# rev_beta_03_1H_smd_ab4.net
KiCad netlist of a schematic drawn in EAGLE
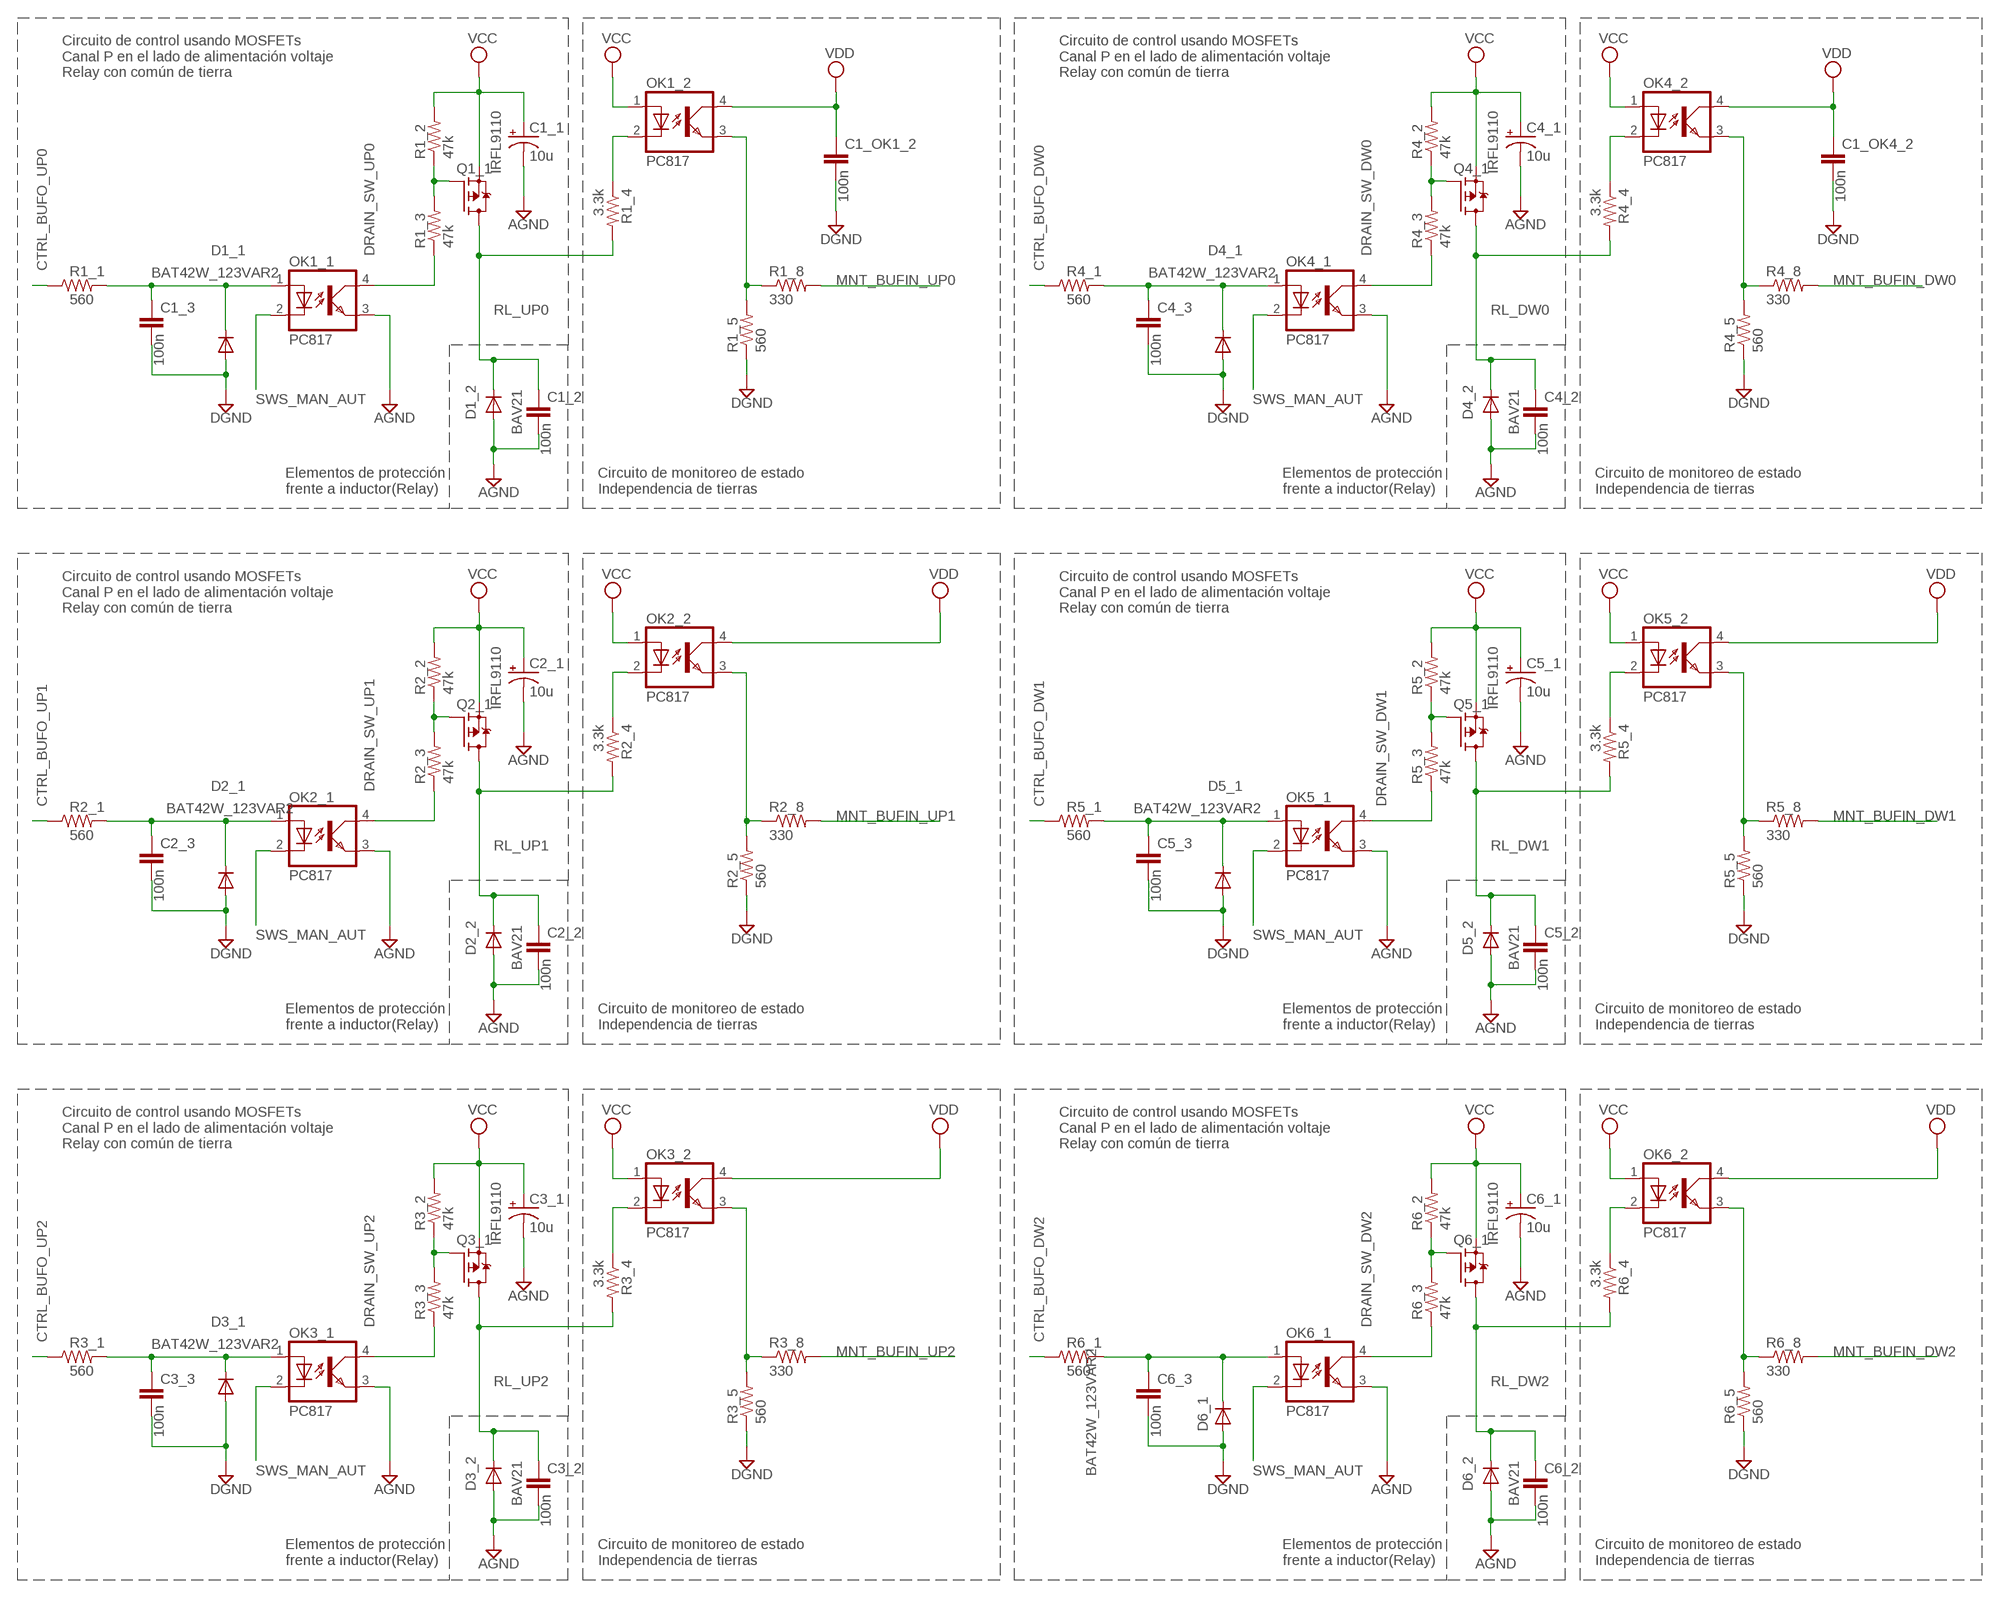
[diagram p0: schematic, sheet 1]
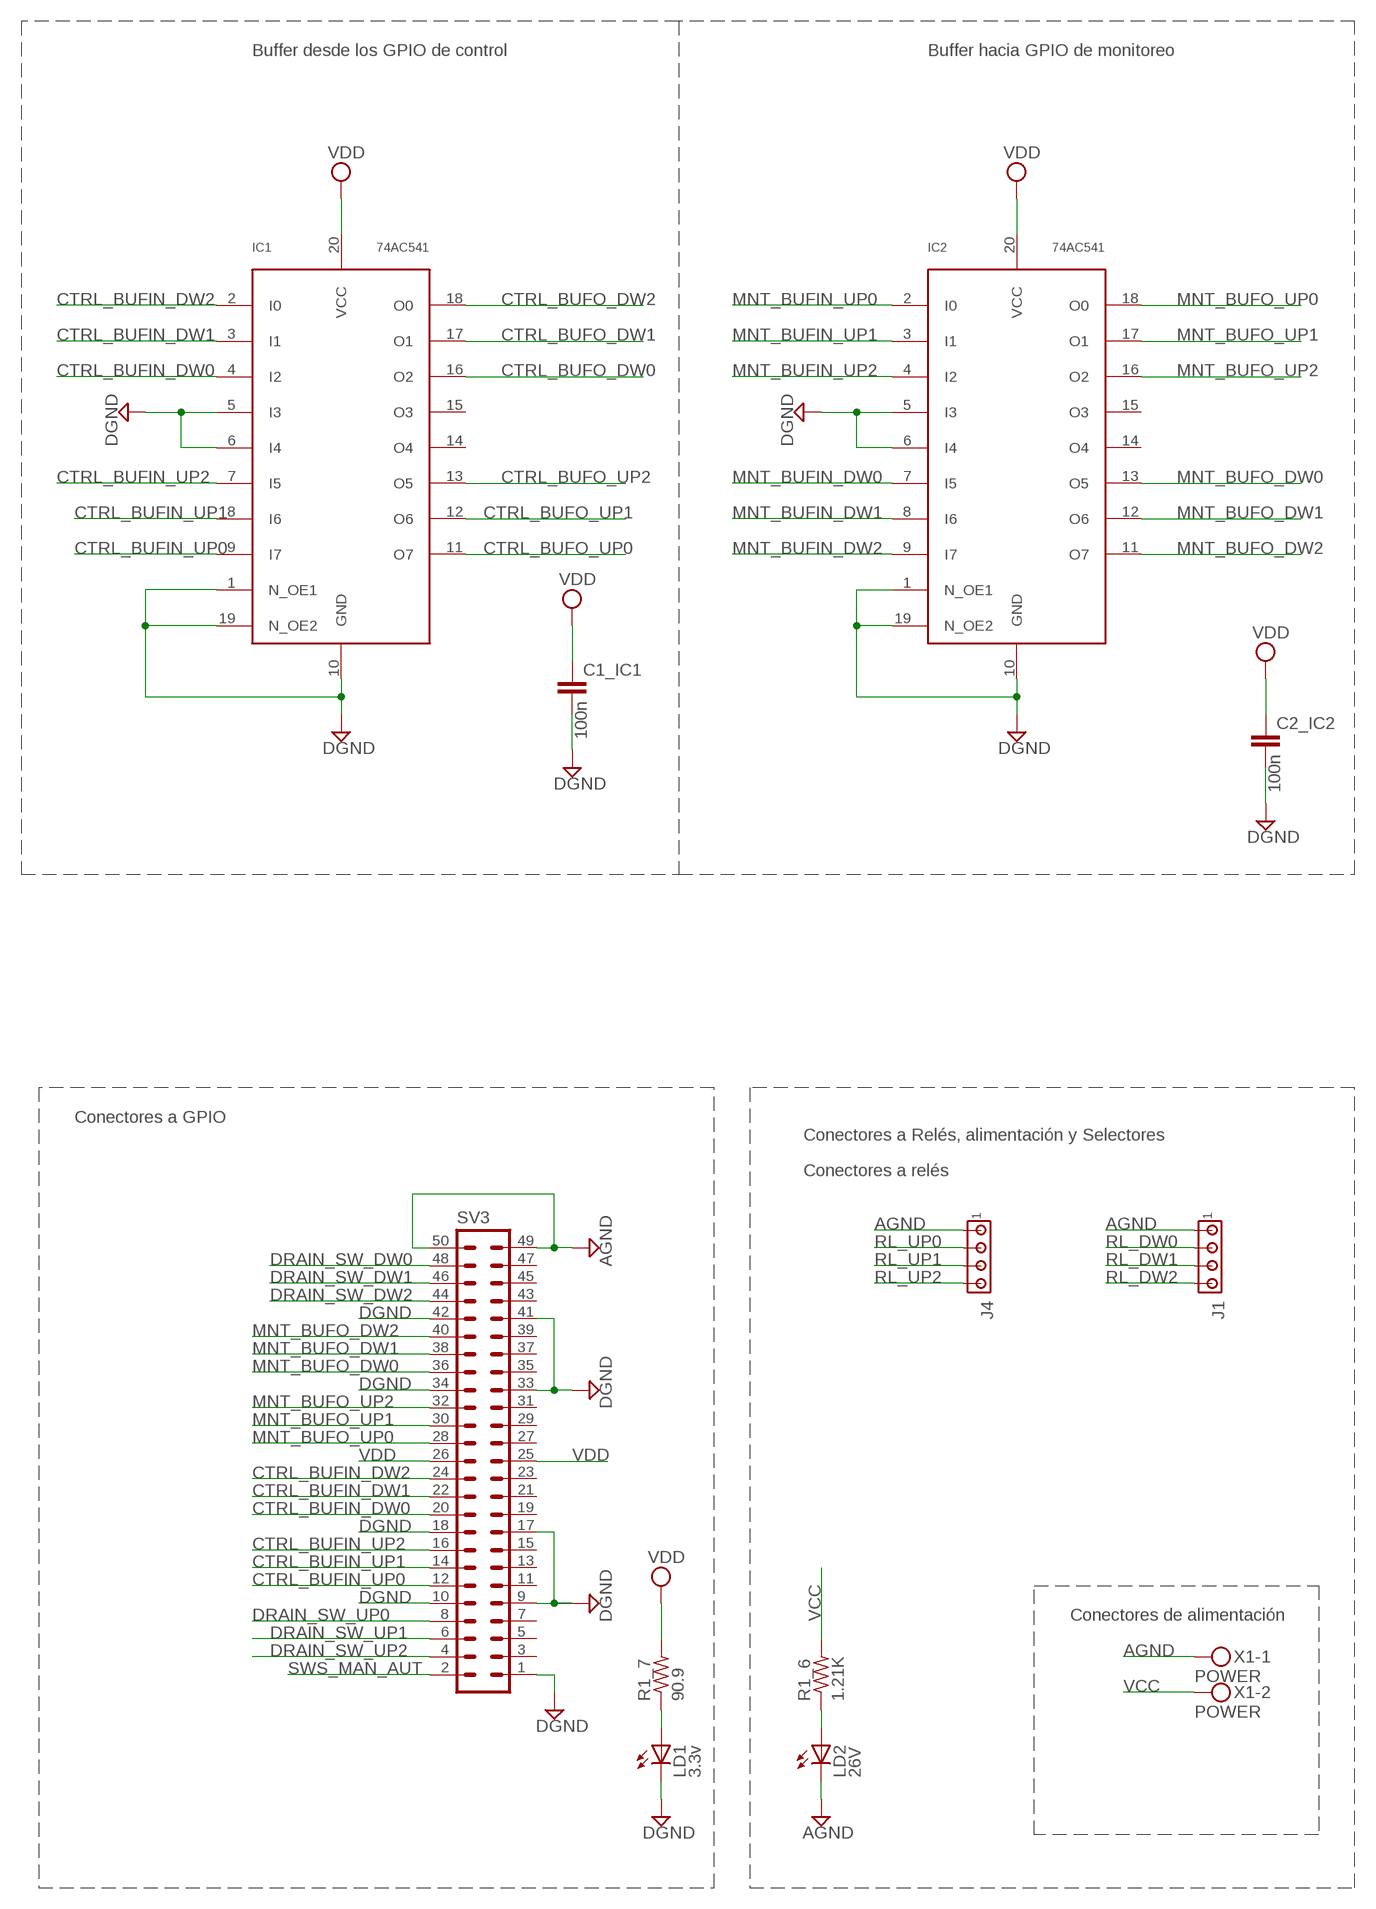
[diagram p1: schematic, sheet 2]

(export (version "E")
  (design (tool "Eeschema 10.0.6"))
  (components
    (comp (ref "C1_IC1")
      (value "100n")
      (footprint "eagle-import:C1206")
      (libsource (lib "eagle-import") (part "C-EUC1206"))
    )
    (comp (ref "C2_IC2")
      (value "100n")
      (footprint "eagle-import:C1206")
      (libsource (lib "eagle-import") (part "C-EUC1206"))
    )
    (comp (ref "IC1")
      (value "74AC541")
      (footprint "eagle-import:SOIC-20DW")
      (fields (field (name "MPN") "74AC541SC"))
      (libsource (lib "eagle-import") (part "74AC541"))
    )
    (comp (ref "IC2")
      (value "74AC541")
      (footprint "eagle-import:SOIC-20DW")
      (fields (field (name "MPN") "74AC541SC"))
      (libsource (lib "eagle-import") (part "74AC541"))
    )
    (comp (ref "J1")
      (value "MTA04-156")
      (footprint "eagle-import:1X4MTA")
      (libsource (lib "eagle-import") (part "MTA04-156"))
    )
    (comp (ref "J4")
      (value "MTA04-156")
      (footprint "eagle-import:1X4MTA")
      (libsource (lib "eagle-import") (part "MTA04-156"))
    )
    (comp (ref "LD1")
      (value "3.3v")
      (footprint "eagle-import:CHIPLED_0603")
      (libsource (lib "eagle-import") (part "LEDCHIPLED_0603"))
    )
    (comp (ref "LD2")
      (value "26V")
      (footprint "eagle-import:CHIPLED_0603")
      (libsource (lib "eagle-import") (part "LEDCHIPLED_0603"))
    )
    (comp (ref "R1_6")
      (value "1.21K")
      (footprint "eagle-import:R1206")
      (libsource (lib "eagle-import") (part "R-US_R1206"))
    )
    (comp (ref "R1_7")
      (value "90.9")
      (footprint "eagle-import:R1206")
      (libsource (lib "eagle-import") (part "R-US_R1206"))
    )
    (comp (ref "SV3")
      (value "ML50\"")
      (footprint "eagle-import:ML50")
      (libsource (lib "eagle-import") (part "ML50{dblquote}"))
    )
    (comp (ref "X1")
      (value "POWER")
      (footprint "eagle-import:MKDSN1,5_2-5,08")
      (libsource (lib "eagle-import") (part "MKDSN1,5/2-5,08"))
    )
    (comp (ref "C1_1")
      (value "10u")
      (footprint "eagle-import:153CLV-0605")
      (libsource (lib "eagle-import") (part "CPOL-US153CLV-0605"))
    )
    (comp (ref "C1_2")
      (value "100n")
      (footprint "eagle-import:C1206")
      (libsource (lib "eagle-import") (part "C-EUC1206"))
    )
    (comp (ref "C1_3")
      (value "100n")
      (footprint "eagle-import:C1206")
      (libsource (lib "eagle-import") (part "C-EUC1206"))
    )
    (comp (ref "C1_OK1_2")
      (value "100n")
      (footprint "eagle-import:C1206")
      (libsource (lib "eagle-import") (part "C-EUC1206"))
    )
    (comp (ref "C1_OK4_2")
      (value "100n")
      (footprint "eagle-import:C1206")
      (libsource (lib "eagle-import") (part "C-EUC1206"))
    )
    (comp (ref "C2_1")
      (value "10u")
      (footprint "eagle-import:153CLV-0605")
      (libsource (lib "eagle-import") (part "CPOL-US153CLV-0605"))
    )
    (comp (ref "C2_2")
      (value "100n")
      (footprint "eagle-import:C1206")
      (libsource (lib "eagle-import") (part "C-EUC1206"))
    )
    (comp (ref "C2_3")
      (value "100n")
      (footprint "eagle-import:C1206")
      (libsource (lib "eagle-import") (part "C-EUC1206"))
    )
    (comp (ref "C3_1")
      (value "10u")
      (footprint "eagle-import:153CLV-0605")
      (libsource (lib "eagle-import") (part "CPOL-US153CLV-0605"))
    )
    (comp (ref "C3_2")
      (value "100n")
      (footprint "eagle-import:C1206")
      (libsource (lib "eagle-import") (part "C-EUC1206"))
    )
    (comp (ref "C3_3")
      (value "100n")
      (footprint "eagle-import:C1206")
      (libsource (lib "eagle-import") (part "C-EUC1206"))
    )
    (comp (ref "C4_1")
      (value "10u")
      (footprint "eagle-import:153CLV-0605")
      (libsource (lib "eagle-import") (part "CPOL-US153CLV-0605"))
    )
    (comp (ref "C4_2")
      (value "100n")
      (footprint "eagle-import:C1206")
      (libsource (lib "eagle-import") (part "C-EUC1206"))
    )
    (comp (ref "C4_3")
      (value "100n")
      (footprint "eagle-import:C1206")
      (libsource (lib "eagle-import") (part "C-EUC1206"))
    )
    (comp (ref "C5_1")
      (value "10u")
      (footprint "eagle-import:153CLV-0605")
      (libsource (lib "eagle-import") (part "CPOL-US153CLV-0605"))
    )
    (comp (ref "C5_2")
      (value "100n")
      (footprint "eagle-import:C1206")
      (libsource (lib "eagle-import") (part "C-EUC1206"))
    )
    (comp (ref "C5_3")
      (value "100n")
      (footprint "eagle-import:C1206")
      (libsource (lib "eagle-import") (part "C-EUC1206"))
    )
    (comp (ref "C6_1")
      (value "10u")
      (footprint "eagle-import:153CLV-0605")
      (libsource (lib "eagle-import") (part "CPOL-US153CLV-0605"))
    )
    (comp (ref "C6_2")
      (value "100n")
      (footprint "eagle-import:C1206")
      (libsource (lib "eagle-import") (part "C-EUC1206"))
    )
    (comp (ref "C6_3")
      (value "100n")
      (footprint "eagle-import:C1206")
      (libsource (lib "eagle-import") (part "C-EUC1206"))
    )
    (comp (ref "D1_1")
      (value "BAT42W_123VAR2")
      (footprint "eagle-import:SOD-523F")
      (libsource (lib "eagle-import") (part "BAT42W_123VAR2"))
    )
    (comp (ref "D1_2")
      (value "BAV21")
      (footprint "eagle-import:DO-35")
      (fields (field (name "MPN") "BAV21_T50R"))
      (libsource (lib "eagle-import") (part "BAV21"))
    )
    (comp (ref "D2_1")
      (value "BAT42W_123VAR2")
      (footprint "eagle-import:SOD-523F")
      (libsource (lib "eagle-import") (part "BAT42W_123VAR2"))
    )
    (comp (ref "D2_2")
      (value "BAV21")
      (footprint "eagle-import:DO-35")
      (fields (field (name "MPN") "BAV21_T50R"))
      (libsource (lib "eagle-import") (part "BAV21"))
    )
    (comp (ref "D3_1")
      (value "BAT42W_123VAR2")
      (footprint "eagle-import:SOD-523F")
      (libsource (lib "eagle-import") (part "BAT42W_123VAR2"))
    )
    (comp (ref "D3_2")
      (value "BAV21")
      (footprint "eagle-import:DO-35")
      (fields (field (name "MPN") "BAV21_T50R"))
      (libsource (lib "eagle-import") (part "BAV21"))
    )
    (comp (ref "D4_1")
      (value "BAT42W_123VAR2")
      (footprint "eagle-import:SOD-523F")
      (libsource (lib "eagle-import") (part "BAT42W_123VAR2"))
    )
    (comp (ref "D4_2")
      (value "BAV21")
      (footprint "eagle-import:DO-35")
      (fields (field (name "MPN") "BAV21_T50R"))
      (libsource (lib "eagle-import") (part "BAV21"))
    )
    (comp (ref "D5_1")
      (value "BAT42W_123VAR2")
      (footprint "eagle-import:SOD-523F")
      (libsource (lib "eagle-import") (part "BAT42W_123VAR2"))
    )
    (comp (ref "D5_2")
      (value "BAV21")
      (footprint "eagle-import:DO-35")
      (fields (field (name "MPN") "BAV21_T50R"))
      (libsource (lib "eagle-import") (part "BAV21"))
    )
    (comp (ref "D6_1")
      (value "BAT42W_123VAR2")
      (footprint "eagle-import:SOD-523F")
      (libsource (lib "eagle-import") (part "BAT42W_123VAR2"))
    )
    (comp (ref "D6_2")
      (value "BAV21")
      (footprint "eagle-import:DO-35")
      (fields (field (name "MPN") "BAV21_T50R"))
      (libsource (lib "eagle-import") (part "BAV21"))
    )
    (comp (ref "OK1_1")
      (value "PC817")
      (footprint "eagle-import:DIL04")
      (fields (field (name "MPN") "PC817X4J000F"))
      (libsource (lib "eagle-import") (part "PC817"))
    )
    (comp (ref "OK1_2")
      (value "PC817")
      (footprint "eagle-import:DIL04")
      (fields (field (name "MPN") "PC817X4J000F"))
      (libsource (lib "eagle-import") (part "PC817"))
    )
    (comp (ref "OK2_1")
      (value "PC817")
      (footprint "eagle-import:DIL04")
      (fields (field (name "MPN") "PC817X4J000F"))
      (libsource (lib "eagle-import") (part "PC817"))
    )
    (comp (ref "OK2_2")
      (value "PC817")
      (footprint "eagle-import:DIL04")
      (fields (field (name "MPN") "PC817X4J000F"))
      (libsource (lib "eagle-import") (part "PC817"))
    )
    (comp (ref "OK3_1")
      (value "PC817")
      (footprint "eagle-import:DIL04")
      (fields (field (name "MPN") "PC817X4J000F"))
      (libsource (lib "eagle-import") (part "PC817"))
    )
    (comp (ref "OK3_2")
      (value "PC817")
      (footprint "eagle-import:DIL04")
      (fields (field (name "MPN") "PC817X4J000F"))
      (libsource (lib "eagle-import") (part "PC817"))
    )
    (comp (ref "OK4_1")
      (value "PC817")
      (footprint "eagle-import:DIL04")
      (fields (field (name "MPN") "PC817X4J000F"))
      (libsource (lib "eagle-import") (part "PC817"))
    )
    (comp (ref "OK4_2")
      (value "PC817")
      (footprint "eagle-import:DIL04")
      (fields (field (name "MPN") "PC817X4J000F"))
      (libsource (lib "eagle-import") (part "PC817"))
    )
    (comp (ref "OK5_1")
      (value "PC817")
      (footprint "eagle-import:DIL04")
      (fields (field (name "MPN") "PC817X4J000F"))
      (libsource (lib "eagle-import") (part "PC817"))
    )
    (comp (ref "OK5_2")
      (value "PC817")
      (footprint "eagle-import:DIL04")
      (fields (field (name "MPN") "PC817X4J000F"))
      (libsource (lib "eagle-import") (part "PC817"))
    )
    (comp (ref "OK6_1")
      (value "PC817")
      (footprint "eagle-import:DIL04")
      (fields (field (name "MPN") "PC817X4J000F"))
      (libsource (lib "eagle-import") (part "PC817"))
    )
    (comp (ref "OK6_2")
      (value "PC817")
      (footprint "eagle-import:DIL04")
      (fields (field (name "MPN") "PC817X4J000F"))
      (libsource (lib "eagle-import") (part "PC817"))
    )
    (comp (ref "Q1_1")
      (value "IRFL9110")
      (footprint "eagle-import:SOT-223")
      (fields (field (name "MPN") "IRFL9110TRPBF"))
      (libsource (lib "eagle-import") (part "IRFL9110"))
    )
    (comp (ref "Q2_1")
      (value "IRFL9110")
      (footprint "eagle-import:SOT-223")
      (fields (field (name "MPN") "IRFL9110TRPBF"))
      (libsource (lib "eagle-import") (part "IRFL9110"))
    )
    (comp (ref "Q3_1")
      (value "IRFL9110")
      (footprint "eagle-import:SOT-223")
      (fields (field (name "MPN") "IRFL9110TRPBF"))
      (libsource (lib "eagle-import") (part "IRFL9110"))
    )
    (comp (ref "Q4_1")
      (value "IRFL9110")
      (footprint "eagle-import:SOT-223")
      (fields (field (name "MPN") "IRFL9110TRPBF"))
      (libsource (lib "eagle-import") (part "IRFL9110"))
    )
    (comp (ref "Q5_1")
      (value "IRFL9110")
      (footprint "eagle-import:SOT-223")
      (fields (field (name "MPN") "IRFL9110TRPBF"))
      (libsource (lib "eagle-import") (part "IRFL9110"))
    )
    (comp (ref "Q6_1")
      (value "IRFL9110")
      (footprint "eagle-import:SOT-223")
      (fields (field (name "MPN") "IRFL9110TRPBF"))
      (libsource (lib "eagle-import") (part "IRFL9110"))
    )
    (comp (ref "R1_1")
      (value "560")
      (footprint "eagle-import:R1206")
      (libsource (lib "eagle-import") (part "R-US_R1206"))
    )
    (comp (ref "R1_2")
      (value "47k")
      (footprint "eagle-import:0207_10")
      (libsource (lib "eagle-import") (part "R-US_0207/10"))
    )
    (comp (ref "R1_3")
      (value "47k")
      (footprint "eagle-import:R1206")
      (libsource (lib "eagle-import") (part "R-US_R1206"))
    )
    (comp (ref "R1_4")
      (value "3.3k")
      (footprint "eagle-import:R1206")
      (libsource (lib "eagle-import") (part "R-US_R1206"))
    )
    (comp (ref "R1_5")
      (value "560")
      (footprint "eagle-import:R1206")
      (libsource (lib "eagle-import") (part "R-US_R1206"))
    )
    (comp (ref "R1_8")
      (value "330")
      (footprint "eagle-import:R1206")
      (libsource (lib "eagle-import") (part "R-US_R1206"))
    )
    (comp (ref "R2_1")
      (value "560")
      (footprint "eagle-import:R1206")
      (libsource (lib "eagle-import") (part "R-US_R1206"))
    )
    (comp (ref "R2_2")
      (value "47k")
      (footprint "eagle-import:0207_10")
      (libsource (lib "eagle-import") (part "R-US_0207/10"))
    )
    (comp (ref "R2_3")
      (value "47k")
      (footprint "eagle-import:R1206")
      (libsource (lib "eagle-import") (part "R-US_R1206"))
    )
    (comp (ref "R2_4")
      (value "3.3k")
      (footprint "eagle-import:R1206")
      (libsource (lib "eagle-import") (part "R-US_R1206"))
    )
    (comp (ref "R2_5")
      (value "560")
      (footprint "eagle-import:R1206")
      (libsource (lib "eagle-import") (part "R-US_R1206"))
    )
    (comp (ref "R2_8")
      (value "330")
      (footprint "eagle-import:R1206")
      (libsource (lib "eagle-import") (part "R-US_R1206"))
    )
    (comp (ref "R3_1")
      (value "560")
      (footprint "eagle-import:R1206")
      (libsource (lib "eagle-import") (part "R-US_R1206"))
    )
    (comp (ref "R3_2")
      (value "47k")
      (footprint "eagle-import:0207_10")
      (libsource (lib "eagle-import") (part "R-US_0207/10"))
    )
    (comp (ref "R3_3")
      (value "47k")
      (footprint "eagle-import:R1206")
      (libsource (lib "eagle-import") (part "R-US_R1206"))
    )
    (comp (ref "R3_4")
      (value "3.3k")
      (footprint "eagle-import:R1206")
      (libsource (lib "eagle-import") (part "R-US_R1206"))
    )
    (comp (ref "R3_5")
      (value "560")
      (footprint "eagle-import:R1206")
      (libsource (lib "eagle-import") (part "R-US_R1206"))
    )
    (comp (ref "R3_8")
      (value "330")
      (footprint "eagle-import:R1206")
      (libsource (lib "eagle-import") (part "R-US_R1206"))
    )
    (comp (ref "R4_1")
      (value "560")
      (footprint "eagle-import:R1206")
      (libsource (lib "eagle-import") (part "R-US_R1206"))
    )
    (comp (ref "R4_2")
      (value "47k")
      (footprint "eagle-import:0207_10")
      (libsource (lib "eagle-import") (part "R-US_0207/10"))
    )
    (comp (ref "R4_3")
      (value "47k")
      (footprint "eagle-import:R1206")
      (libsource (lib "eagle-import") (part "R-US_R1206"))
    )
    (comp (ref "R4_4")
      (value "3.3k")
      (footprint "eagle-import:R1206")
      (libsource (lib "eagle-import") (part "R-US_R1206"))
    )
    (comp (ref "R4_5")
      (value "560")
      (footprint "eagle-import:R1206")
      (libsource (lib "eagle-import") (part "R-US_R1206"))
    )
    (comp (ref "R4_8")
      (value "330")
      (footprint "eagle-import:R1206")
      (libsource (lib "eagle-import") (part "R-US_R1206"))
    )
    (comp (ref "R5_1")
      (value "560")
      (footprint "eagle-import:R1206")
      (libsource (lib "eagle-import") (part "R-US_R1206"))
    )
    (comp (ref "R5_2")
      (value "47k")
      (footprint "eagle-import:0207_10")
      (libsource (lib "eagle-import") (part "R-US_0207/10"))
    )
    (comp (ref "R5_3")
      (value "47k")
      (footprint "eagle-import:R1206")
      (libsource (lib "eagle-import") (part "R-US_R1206"))
    )
    (comp (ref "R5_4")
      (value "3.3k")
      (footprint "eagle-import:R1206")
      (libsource (lib "eagle-import") (part "R-US_R1206"))
    )
    (comp (ref "R5_5")
      (value "560")
      (footprint "eagle-import:R1206")
      (libsource (lib "eagle-import") (part "R-US_R1206"))
    )
    (comp (ref "R5_8")
      (value "330")
      (footprint "eagle-import:R1206")
      (libsource (lib "eagle-import") (part "R-US_R1206"))
    )
    (comp (ref "R6_1")
      (value "560")
      (footprint "eagle-import:R1206")
      (libsource (lib "eagle-import") (part "R-US_R1206"))
    )
    (comp (ref "R6_2")
      (value "47k")
      (footprint "eagle-import:0207_10")
      (libsource (lib "eagle-import") (part "R-US_0207/10"))
    )
    (comp (ref "R6_3")
      (value "47k")
      (footprint "eagle-import:R1206")
      (libsource (lib "eagle-import") (part "R-US_R1206"))
    )
    (comp (ref "R6_4")
      (value "3.3k")
      (footprint "eagle-import:R1206")
      (libsource (lib "eagle-import") (part "R-US_R1206"))
    )
    (comp (ref "R6_5")
      (value "560")
      (footprint "eagle-import:R1206")
      (libsource (lib "eagle-import") (part "R-US_R1206"))
    )
    (comp (ref "R6_8")
      (value "330")
      (footprint "eagle-import:R1206")
      (libsource (lib "eagle-import") (part "R-US_R1206"))
    )
  )
  (nets
    (net (code "1") (name "AGND") (class "Default")
      (node (ref "C1_1") (pin "-") (pinfunction "-_-") (pintype "passive"))
      (node (ref "C1_2") (pin "2") (pinfunction "2_2") (pintype "passive"))
      (node (ref "C2_1") (pin "-") (pinfunction "-_-") (pintype "passive"))
      (node (ref "C2_2") (pin "2") (pinfunction "2_2") (pintype "passive"))
      (node (ref "C3_1") (pin "-") (pinfunction "-_-") (pintype "passive"))
      (node (ref "C3_2") (pin "2") (pinfunction "2_2") (pintype "passive"))
      (node (ref "C4_1") (pin "-") (pinfunction "-_-") (pintype "passive"))
      (node (ref "C4_2") (pin "2") (pinfunction "2_2") (pintype "passive"))
      (node (ref "C5_1") (pin "-") (pinfunction "-_-") (pintype "passive"))
      (node (ref "C5_2") (pin "2") (pinfunction "2_2") (pintype "passive"))
      (node (ref "C6_1") (pin "-") (pinfunction "-_-") (pintype "passive"))
      (node (ref "C6_2") (pin "2") (pinfunction "2_2") (pintype "passive"))
      (node (ref "D1_2") (pin "A") (pinfunction "A_A") (pintype "passive"))
      (node (ref "D2_2") (pin "A") (pinfunction "A_A") (pintype "passive"))
      (node (ref "D3_2") (pin "A") (pinfunction "A_A") (pintype "passive"))
      (node (ref "D4_2") (pin "A") (pinfunction "A_A") (pintype "passive"))
      (node (ref "D5_2") (pin "A") (pinfunction "A_A") (pintype "passive"))
      (node (ref "D6_2") (pin "A") (pinfunction "A_A") (pintype "passive"))
      (node (ref "J1") (pin "1") (pinfunction "1_1") (pintype "passive"))
      (node (ref "J4") (pin "1") (pinfunction "1_1") (pintype "passive"))
      (node (ref "LD2") (pin "C") (pinfunction "C_C") (pintype "passive"))
      (node (ref "OK1_1") (pin "3") (pinfunction "EMIT_3") (pintype "passive"))
      (node (ref "OK2_1") (pin "3") (pinfunction "EMIT_3") (pintype "passive"))
      (node (ref "OK3_1") (pin "3") (pinfunction "EMIT_3") (pintype "passive"))
      (node (ref "OK4_1") (pin "3") (pinfunction "EMIT_3") (pintype "passive"))
      (node (ref "OK5_1") (pin "3") (pinfunction "EMIT_3") (pintype "passive"))
      (node (ref "OK6_1") (pin "3") (pinfunction "EMIT_3") (pintype "passive"))
      (node (ref "SV3") (pin "49") (pinfunction "49_49") (pintype "passive"))
      (node (ref "SV3") (pin "50") (pinfunction "50_50") (pintype "passive"))
      (node (ref "X1") (pin "1") (pinfunction "KL_1") (pintype "passive"))
    )
    (net (code "2") (name "CTRL_BUFIN_DW0") (class "Default")
      (node (ref "IC1") (pin "4") (pinfunction "I2_4") (pintype "input"))
      (node (ref "SV3") (pin "20") (pinfunction "20_20") (pintype "passive"))
    )
    (net (code "3") (name "CTRL_BUFIN_DW1") (class "Default")
      (node (ref "IC1") (pin "3") (pinfunction "I1_3") (pintype "input"))
      (node (ref "SV3") (pin "22") (pinfunction "22_22") (pintype "passive"))
    )
    (net (code "4") (name "CTRL_BUFIN_DW2") (class "Default")
      (node (ref "IC1") (pin "2") (pinfunction "I0_2") (pintype "input"))
      (node (ref "SV3") (pin "24") (pinfunction "24_24") (pintype "passive"))
    )
    (net (code "5") (name "CTRL_BUFIN_UP0") (class "Default")
      (node (ref "IC1") (pin "9") (pinfunction "I7_9") (pintype "input"))
      (node (ref "SV3") (pin "12") (pinfunction "12_12") (pintype "passive"))
    )
    (net (code "6") (name "CTRL_BUFIN_UP1") (class "Default")
      (node (ref "IC1") (pin "8") (pinfunction "I6_8") (pintype "input"))
      (node (ref "SV3") (pin "14") (pinfunction "14_14") (pintype "passive"))
    )
    (net (code "7") (name "CTRL_BUFIN_UP2") (class "Default")
      (node (ref "IC1") (pin "7") (pinfunction "I5_7") (pintype "input"))
      (node (ref "SV3") (pin "16") (pinfunction "16_16") (pintype "passive"))
    )
    (net (code "8") (name "CTRL_BUFO_DW0") (class "Default")
      (node (ref "IC1") (pin "16") (pinfunction "O2_16") (pintype "output"))
      (node (ref "R4_1") (pin "1") (pinfunction "1_1") (pintype "passive"))
    )
    (net (code "9") (name "CTRL_BUFO_DW1") (class "Default")
      (node (ref "IC1") (pin "17") (pinfunction "O1_17") (pintype "output"))
      (node (ref "R5_1") (pin "1") (pinfunction "1_1") (pintype "passive"))
    )
    (net (code "10") (name "CTRL_BUFO_DW2") (class "Default")
      (node (ref "IC1") (pin "18") (pinfunction "O0_18") (pintype "output"))
      (node (ref "R6_1") (pin "1") (pinfunction "1_1") (pintype "passive"))
    )
    (net (code "11") (name "CTRL_BUFO_UP0") (class "Default")
      (node (ref "IC1") (pin "11") (pinfunction "O7_11") (pintype "output"))
      (node (ref "R1_1") (pin "1") (pinfunction "1_1") (pintype "passive"))
    )
    (net (code "12") (name "CTRL_BUFO_UP1") (class "Default")
      (node (ref "IC1") (pin "12") (pinfunction "O6_12") (pintype "output"))
      (node (ref "R2_1") (pin "1") (pinfunction "1_1") (pintype "passive"))
    )
    (net (code "13") (name "CTRL_BUFO_UP2") (class "Default")
      (node (ref "IC1") (pin "13") (pinfunction "O5_13") (pintype "output"))
      (node (ref "R3_1") (pin "1") (pinfunction "1_1") (pintype "passive"))
    )
    (net (code "14") (name "DGND") (class "Default")
      (node (ref "C1_3") (pin "2") (pinfunction "2_2") (pintype "passive"))
      (node (ref "C1_IC1") (pin "2") (pinfunction "2_2") (pintype "passive"))
      (node (ref "C1_OK1_2") (pin "2") (pinfunction "2_2") (pintype "passive"))
      (node (ref "C1_OK4_2") (pin "2") (pinfunction "2_2") (pintype "passive"))
      (node (ref "C2_3") (pin "2") (pinfunction "2_2") (pintype "passive"))
      (node (ref "C2_IC2") (pin "2") (pinfunction "2_2") (pintype "passive"))
      (node (ref "C3_3") (pin "2") (pinfunction "2_2") (pintype "passive"))
      (node (ref "C4_3") (pin "2") (pinfunction "2_2") (pintype "passive"))
      (node (ref "C5_3") (pin "2") (pinfunction "2_2") (pintype "passive"))
      (node (ref "C6_3") (pin "2") (pinfunction "2_2") (pintype "passive"))
      (node (ref "D1_1") (pin "A") (pinfunction "1_A") (pintype "passive"))
      (node (ref "D2_1") (pin "A") (pinfunction "1_A") (pintype "passive"))
      (node (ref "D3_1") (pin "A") (pinfunction "1_A") (pintype "passive"))
      (node (ref "D4_1") (pin "A") (pinfunction "1_A") (pintype "passive"))
      (node (ref "D5_1") (pin "A") (pinfunction "1_A") (pintype "passive"))
      (node (ref "D6_1") (pin "A") (pinfunction "1_A") (pintype "passive"))
      (node (ref "IC1") (pin "1") (pinfunction "N_OE1_1") (pintype "input"))
      (node (ref "IC1") (pin "10") (pinfunction "GND_10") (pintype "power_in"))
      (node (ref "IC1") (pin "19") (pinfunction "N_OE2_19") (pintype "input"))
      (node (ref "IC1") (pin "5") (pinfunction "I3_5") (pintype "input"))
      (node (ref "IC1") (pin "6") (pinfunction "I4_6") (pintype "input"))
      (node (ref "IC2") (pin "1") (pinfunction "N_OE1_1") (pintype "input"))
      (node (ref "IC2") (pin "10") (pinfunction "GND_10") (pintype "power_in"))
      (node (ref "IC2") (pin "19") (pinfunction "N_OE2_19") (pintype "input"))
      (node (ref "IC2") (pin "5") (pinfunction "I3_5") (pintype "input"))
      (node (ref "IC2") (pin "6") (pinfunction "I4_6") (pintype "input"))
      (node (ref "LD1") (pin "C") (pinfunction "C_C") (pintype "passive"))
      (node (ref "R1_5") (pin "1") (pinfunction "1_1") (pintype "passive"))
      (node (ref "R2_5") (pin "1") (pinfunction "1_1") (pintype "passive"))
      (node (ref "R3_5") (pin "1") (pinfunction "1_1") (pintype "passive"))
      (node (ref "R4_5") (pin "1") (pinfunction "1_1") (pintype "passive"))
      (node (ref "R5_5") (pin "1") (pinfunction "1_1") (pintype "passive"))
      (node (ref "R6_5") (pin "1") (pinfunction "1_1") (pintype "passive"))
      (node (ref "SV3") (pin "1") (pinfunction "1_1") (pintype "passive"))
      (node (ref "SV3") (pin "10") (pinfunction "10_10") (pintype "passive"))
      (node (ref "SV3") (pin "17") (pinfunction "17_17") (pintype "passive"))
      (node (ref "SV3") (pin "18") (pinfunction "18_18") (pintype "passive"))
      (node (ref "SV3") (pin "33") (pinfunction "33_33") (pintype "passive"))
      (node (ref "SV3") (pin "34") (pinfunction "34_34") (pintype "passive"))
      (node (ref "SV3") (pin "41") (pinfunction "41_41") (pintype "passive"))
      (node (ref "SV3") (pin "42") (pinfunction "42_42") (pintype "passive"))
      (node (ref "SV3") (pin "9") (pinfunction "9_9") (pintype "passive"))
    )
    (net (code "15") (name "DRAIN_SW_DW0") (class "Default")
      (node (ref "OK4_1") (pin "4") (pinfunction "COL_4") (pintype "passive"))
      (node (ref "R4_3") (pin "1") (pinfunction "1_1") (pintype "passive"))
      (node (ref "SV3") (pin "48") (pinfunction "48_48") (pintype "passive"))
    )
    (net (code "16") (name "DRAIN_SW_DW1") (class "Default")
      (node (ref "OK5_1") (pin "4") (pinfunction "COL_4") (pintype "passive"))
      (node (ref "R5_3") (pin "1") (pinfunction "1_1") (pintype "passive"))
      (node (ref "SV3") (pin "46") (pinfunction "46_46") (pintype "passive"))
    )
    (net (code "17") (name "DRAIN_SW_DW2") (class "Default")
      (node (ref "OK6_1") (pin "4") (pinfunction "COL_4") (pintype "passive"))
      (node (ref "R6_3") (pin "1") (pinfunction "1_1") (pintype "passive"))
      (node (ref "SV3") (pin "44") (pinfunction "44_44") (pintype "passive"))
    )
    (net (code "18") (name "DRAIN_SW_UP0") (class "Default")
      (node (ref "OK1_1") (pin "4") (pinfunction "COL_4") (pintype "passive"))
      (node (ref "R1_3") (pin "1") (pinfunction "1_1") (pintype "passive"))
      (node (ref "SV3") (pin "8") (pinfunction "8_8") (pintype "passive"))
    )
    (net (code "19") (name "DRAIN_SW_UP1") (class "Default")
      (node (ref "OK2_1") (pin "4") (pinfunction "COL_4") (pintype "passive"))
      (node (ref "R2_3") (pin "1") (pinfunction "1_1") (pintype "passive"))
      (node (ref "SV3") (pin "6") (pinfunction "6_6") (pintype "passive"))
    )
    (net (code "20") (name "DRAIN_SW_UP2") (class "Default")
      (node (ref "OK3_1") (pin "4") (pinfunction "COL_4") (pintype "passive"))
      (node (ref "R3_3") (pin "1") (pinfunction "1_1") (pintype "passive"))
      (node (ref "SV3") (pin "4") (pinfunction "4_4") (pintype "passive"))
    )
    (net (code "21") (name "MNT_BUFIN_DW0") (class "Default")
      (node (ref "IC2") (pin "7") (pinfunction "I5_7") (pintype "input"))
      (node (ref "R4_8") (pin "2") (pinfunction "2_2") (pintype "passive"))
    )
    (net (code "22") (name "MNT_BUFIN_DW1") (class "Default")
      (node (ref "IC2") (pin "8") (pinfunction "I6_8") (pintype "input"))
      (node (ref "R5_8") (pin "2") (pinfunction "2_2") (pintype "passive"))
    )
    (net (code "23") (name "MNT_BUFIN_DW2") (class "Default")
      (node (ref "IC2") (pin "9") (pinfunction "I7_9") (pintype "input"))
      (node (ref "R6_8") (pin "2") (pinfunction "2_2") (pintype "passive"))
    )
    (net (code "24") (name "MNT_BUFIN_UP0") (class "Default")
      (node (ref "IC2") (pin "2") (pinfunction "I0_2") (pintype "input"))
      (node (ref "R1_8") (pin "2") (pinfunction "2_2") (pintype "passive"))
    )
    (net (code "25") (name "MNT_BUFIN_UP1") (class "Default")
      (node (ref "IC2") (pin "3") (pinfunction "I1_3") (pintype "input"))
      (node (ref "R2_8") (pin "2") (pinfunction "2_2") (pintype "passive"))
    )
    (net (code "26") (name "MNT_BUFIN_UP2") (class "Default")
      (node (ref "IC2") (pin "4") (pinfunction "I2_4") (pintype "input"))
      (node (ref "R3_8") (pin "2") (pinfunction "2_2") (pintype "passive"))
    )
    (net (code "27") (name "MNT_BUFO_DW0") (class "Default")
      (node (ref "IC2") (pin "13") (pinfunction "O5_13") (pintype "output"))
      (node (ref "SV3") (pin "36") (pinfunction "36_36") (pintype "passive"))
    )
    (net (code "28") (name "MNT_BUFO_DW1") (class "Default")
      (node (ref "IC2") (pin "12") (pinfunction "O6_12") (pintype "output"))
      (node (ref "SV3") (pin "38") (pinfunction "38_38") (pintype "passive"))
    )
    (net (code "29") (name "MNT_BUFO_DW2") (class "Default")
      (node (ref "IC2") (pin "11") (pinfunction "O7_11") (pintype "output"))
      (node (ref "SV3") (pin "40") (pinfunction "40_40") (pintype "passive"))
    )
    (net (code "30") (name "MNT_BUFO_UP0") (class "Default")
      (node (ref "IC2") (pin "18") (pinfunction "O0_18") (pintype "output"))
      (node (ref "SV3") (pin "28") (pinfunction "28_28") (pintype "passive"))
    )
    (net (code "31") (name "MNT_BUFO_UP1") (class "Default")
      (node (ref "IC2") (pin "17") (pinfunction "O1_17") (pintype "output"))
      (node (ref "SV3") (pin "30") (pinfunction "30_30") (pintype "passive"))
    )
    (net (code "32") (name "MNT_BUFO_UP2") (class "Default")
      (node (ref "IC2") (pin "16") (pinfunction "O2_16") (pintype "output"))
      (node (ref "SV3") (pin "32") (pinfunction "32_32") (pintype "passive"))
    )
    (net (code "33") (name "Net-(D1_1-2)") (class "Default")
      (node (ref "C1_3") (pin "1") (pinfunction "1_1") (pintype "passive"))
      (node (ref "D1_1") (pin "C") (pinfunction "2_C") (pintype "passive"))
      (node (ref "OK1_1") (pin "1") (pinfunction "A_1") (pintype "passive"))
      (node (ref "R1_1") (pin "2") (pinfunction "2_2") (pintype "passive"))
    )
    (net (code "34") (name "Net-(D2_1-2)") (class "Default")
      (node (ref "C2_3") (pin "1") (pinfunction "1_1") (pintype "passive"))
      (node (ref "D2_1") (pin "C") (pinfunction "2_C") (pintype "passive"))
      (node (ref "OK2_1") (pin "1") (pinfunction "A_1") (pintype "passive"))
      (node (ref "R2_1") (pin "2") (pinfunction "2_2") (pintype "passive"))
    )
    (net (code "35") (name "Net-(D3_1-2)") (class "Default")
      (node (ref "C3_3") (pin "1") (pinfunction "1_1") (pintype "passive"))
      (node (ref "D3_1") (pin "C") (pinfunction "2_C") (pintype "passive"))
      (node (ref "OK3_1") (pin "1") (pinfunction "A_1") (pintype "passive"))
      (node (ref "R3_1") (pin "2") (pinfunction "2_2") (pintype "passive"))
    )
    (net (code "36") (name "Net-(D4_1-2)") (class "Default")
      (node (ref "C4_3") (pin "1") (pinfunction "1_1") (pintype "passive"))
      (node (ref "D4_1") (pin "C") (pinfunction "2_C") (pintype "passive"))
      (node (ref "OK4_1") (pin "1") (pinfunction "A_1") (pintype "passive"))
      (node (ref "R4_1") (pin "2") (pinfunction "2_2") (pintype "passive"))
    )
    (net (code "37") (name "Net-(D5_1-2)") (class "Default")
      (node (ref "C5_3") (pin "1") (pinfunction "1_1") (pintype "passive"))
      (node (ref "D5_1") (pin "C") (pinfunction "2_C") (pintype "passive"))
      (node (ref "OK5_1") (pin "1") (pinfunction "A_1") (pintype "passive"))
      (node (ref "R5_1") (pin "2") (pinfunction "2_2") (pintype "passive"))
    )
    (net (code "38") (name "Net-(D6_1-2)") (class "Default")
      (node (ref "C6_3") (pin "1") (pinfunction "1_1") (pintype "passive"))
      (node (ref "D6_1") (pin "C") (pinfunction "2_C") (pintype "passive"))
      (node (ref "OK6_1") (pin "1") (pinfunction "A_1") (pintype "passive"))
      (node (ref "R6_1") (pin "2") (pinfunction "2_2") (pintype "passive"))
    )
    (net (code "39") (name "Net-(LD1-PadA)") (class "Default")
      (node (ref "LD1") (pin "A") (pinfunction "A_A") (pintype "passive"))
      (node (ref "R1_7") (pin "1") (pinfunction "1_1") (pintype "passive"))
    )
    (net (code "40") (name "Net-(LD2-PadA)") (class "Default")
      (node (ref "LD2") (pin "A") (pinfunction "A_A") (pintype "passive"))
      (node (ref "R1_6") (pin "1") (pinfunction "1_1") (pintype "passive"))
    )
    (net (code "41") (name "Net-(OK1_2-C)") (class "Default")
      (node (ref "OK1_2") (pin "2") (pinfunction "C_2") (pintype "passive"))
      (node (ref "R1_4") (pin "1") (pinfunction "1_1") (pintype "passive"))
    )
    (net (code "42") (name "Net-(OK1_2-EMIT)") (class "Default")
      (node (ref "OK1_2") (pin "3") (pinfunction "EMIT_3") (pintype "passive"))
      (node (ref "R1_5") (pin "2") (pinfunction "2_2") (pintype "passive"))
      (node (ref "R1_8") (pin "1") (pinfunction "1_1") (pintype "passive"))
    )
    (net (code "43") (name "Net-(OK2_2-C)") (class "Default")
      (node (ref "OK2_2") (pin "2") (pinfunction "C_2") (pintype "passive"))
      (node (ref "R2_4") (pin "1") (pinfunction "1_1") (pintype "passive"))
    )
    (net (code "44") (name "Net-(OK2_2-EMIT)") (class "Default")
      (node (ref "OK2_2") (pin "3") (pinfunction "EMIT_3") (pintype "passive"))
      (node (ref "R2_5") (pin "2") (pinfunction "2_2") (pintype "passive"))
      (node (ref "R2_8") (pin "1") (pinfunction "1_1") (pintype "passive"))
    )
    (net (code "45") (name "Net-(OK3_2-C)") (class "Default")
      (node (ref "OK3_2") (pin "2") (pinfunction "C_2") (pintype "passive"))
      (node (ref "R3_4") (pin "1") (pinfunction "1_1") (pintype "passive"))
    )
    (net (code "46") (name "Net-(OK3_2-EMIT)") (class "Default")
      (node (ref "OK3_2") (pin "3") (pinfunction "EMIT_3") (pintype "passive"))
      (node (ref "R3_5") (pin "2") (pinfunction "2_2") (pintype "passive"))
      (node (ref "R3_8") (pin "1") (pinfunction "1_1") (pintype "passive"))
    )
    (net (code "47") (name "Net-(OK4_2-C)") (class "Default")
      (node (ref "OK4_2") (pin "2") (pinfunction "C_2") (pintype "passive"))
      (node (ref "R4_4") (pin "1") (pinfunction "1_1") (pintype "passive"))
    )
    (net (code "48") (name "Net-(OK4_2-EMIT)") (class "Default")
      (node (ref "OK4_2") (pin "3") (pinfunction "EMIT_3") (pintype "passive"))
      (node (ref "R4_5") (pin "2") (pinfunction "2_2") (pintype "passive"))
      (node (ref "R4_8") (pin "1") (pinfunction "1_1") (pintype "passive"))
    )
    (net (code "49") (name "Net-(OK5_2-C)") (class "Default")
      (node (ref "OK5_2") (pin "2") (pinfunction "C_2") (pintype "passive"))
      (node (ref "R5_4") (pin "1") (pinfunction "1_1") (pintype "passive"))
    )
    (net (code "50") (name "Net-(OK5_2-EMIT)") (class "Default")
      (node (ref "OK5_2") (pin "3") (pinfunction "EMIT_3") (pintype "passive"))
      (node (ref "R5_5") (pin "2") (pinfunction "2_2") (pintype "passive"))
      (node (ref "R5_8") (pin "1") (pinfunction "1_1") (pintype "passive"))
    )
    (net (code "51") (name "Net-(OK6_2-C)") (class "Default")
      (node (ref "OK6_2") (pin "2") (pinfunction "C_2") (pintype "passive"))
      (node (ref "R6_4") (pin "1") (pinfunction "1_1") (pintype "passive"))
    )
    (net (code "52") (name "Net-(OK6_2-EMIT)") (class "Default")
      (node (ref "OK6_2") (pin "3") (pinfunction "EMIT_3") (pintype "passive"))
      (node (ref "R6_5") (pin "2") (pinfunction "2_2") (pintype "passive"))
      (node (ref "R6_8") (pin "1") (pinfunction "1_1") (pintype "passive"))
    )
    (net (code "53") (name "Net-(Q1_1-G)") (class "Default")
      (node (ref "Q1_1") (pin "1") (pinfunction "G_1") (pintype "passive"))
      (node (ref "R1_2") (pin "1") (pinfunction "1_1") (pintype "passive"))
      (node (ref "R1_3") (pin "2") (pinfunction "2_2") (pintype "passive"))
    )
    (net (code "54") (name "Net-(Q2_1-G)") (class "Default")
      (node (ref "Q2_1") (pin "1") (pinfunction "G_1") (pintype "passive"))
      (node (ref "R2_2") (pin "1") (pinfunction "1_1") (pintype "passive"))
      (node (ref "R2_3") (pin "2") (pinfunction "2_2") (pintype "passive"))
    )
    (net (code "55") (name "Net-(Q3_1-G)") (class "Default")
      (node (ref "Q3_1") (pin "1") (pinfunction "G_1") (pintype "passive"))
      (node (ref "R3_2") (pin "1") (pinfunction "1_1") (pintype "passive"))
      (node (ref "R3_3") (pin "2") (pinfunction "2_2") (pintype "passive"))
    )
    (net (code "56") (name "Net-(Q4_1-G)") (class "Default")
      (node (ref "Q4_1") (pin "1") (pinfunction "G_1") (pintype "passive"))
      (node (ref "R4_2") (pin "1") (pinfunction "1_1") (pintype "passive"))
      (node (ref "R4_3") (pin "2") (pinfunction "2_2") (pintype "passive"))
    )
    (net (code "57") (name "Net-(Q5_1-G)") (class "Default")
      (node (ref "Q5_1") (pin "1") (pinfunction "G_1") (pintype "passive"))
      (node (ref "R5_2") (pin "1") (pinfunction "1_1") (pintype "passive"))
      (node (ref "R5_3") (pin "2") (pinfunction "2_2") (pintype "passive"))
    )
    (net (code "58") (name "Net-(Q6_1-G)") (class "Default")
      (node (ref "Q6_1") (pin "1") (pinfunction "G_1") (pintype "passive"))
      (node (ref "R6_2") (pin "1") (pinfunction "1_1") (pintype "passive"))
      (node (ref "R6_3") (pin "2") (pinfunction "2_2") (pintype "passive"))
    )
    (net (code "59") (name "RL_DW0") (class "Default")
      (node (ref "C4_2") (pin "1") (pinfunction "1_1") (pintype "passive"))
      (node (ref "D4_2") (pin "C") (pinfunction "C_C") (pintype "passive"))
      (node (ref "J1") (pin "2") (pinfunction "2_2") (pintype "passive"))
      (node (ref "Q4_1") (pin "2") (pinfunction "D_2") (pintype "passive"))
      (node (ref "Q4_1") (pin "4") (pinfunction "D_4") (pintype "passive"))
      (node (ref "R4_4") (pin "2") (pinfunction "2_2") (pintype "passive"))
    )
    (net (code "60") (name "RL_DW1") (class "Default")
      (node (ref "C5_2") (pin "1") (pinfunction "1_1") (pintype "passive"))
      (node (ref "D5_2") (pin "C") (pinfunction "C_C") (pintype "passive"))
      (node (ref "J1") (pin "3") (pinfunction "3_3") (pintype "passive"))
      (node (ref "Q5_1") (pin "2") (pinfunction "D_2") (pintype "passive"))
      (node (ref "Q5_1") (pin "4") (pinfunction "D_4") (pintype "passive"))
      (node (ref "R5_4") (pin "2") (pinfunction "2_2") (pintype "passive"))
    )
    (net (code "61") (name "RL_DW2") (class "Default")
      (node (ref "C6_2") (pin "1") (pinfunction "1_1") (pintype "passive"))
      (node (ref "D6_2") (pin "C") (pinfunction "C_C") (pintype "passive"))
      (node (ref "J1") (pin "4") (pinfunction "4_4") (pintype "passive"))
      (node (ref "Q6_1") (pin "2") (pinfunction "D_2") (pintype "passive"))
      (node (ref "Q6_1") (pin "4") (pinfunction "D_4") (pintype "passive"))
      (node (ref "R6_4") (pin "2") (pinfunction "2_2") (pintype "passive"))
    )
    (net (code "62") (name "RL_UP0") (class "Default")
      (node (ref "C1_2") (pin "1") (pinfunction "1_1") (pintype "passive"))
      (node (ref "D1_2") (pin "C") (pinfunction "C_C") (pintype "passive"))
      (node (ref "J4") (pin "2") (pinfunction "2_2") (pintype "passive"))
      (node (ref "Q1_1") (pin "2") (pinfunction "D_2") (pintype "passive"))
      (node (ref "Q1_1") (pin "4") (pinfunction "D_4") (pintype "passive"))
      (node (ref "R1_4") (pin "2") (pinfunction "2_2") (pintype "passive"))
    )
    (net (code "63") (name "RL_UP1") (class "Default")
      (node (ref "C2_2") (pin "1") (pinfunction "1_1") (pintype "passive"))
      (node (ref "D2_2") (pin "C") (pinfunction "C_C") (pintype "passive"))
      (node (ref "J4") (pin "3") (pinfunction "3_3") (pintype "passive"))
      (node (ref "Q2_1") (pin "2") (pinfunction "D_2") (pintype "passive"))
      (node (ref "Q2_1") (pin "4") (pinfunction "D_4") (pintype "passive"))
      (node (ref "R2_4") (pin "2") (pinfunction "2_2") (pintype "passive"))
    )
    (net (code "64") (name "RL_UP2") (class "Default")
      (node (ref "C3_2") (pin "1") (pinfunction "1_1") (pintype "passive"))
      (node (ref "D3_2") (pin "C") (pinfunction "C_C") (pintype "passive"))
      (node (ref "J4") (pin "4") (pinfunction "4_4") (pintype "passive"))
      (node (ref "Q3_1") (pin "2") (pinfunction "D_2") (pintype "passive"))
      (node (ref "Q3_1") (pin "4") (pinfunction "D_4") (pintype "passive"))
      (node (ref "R3_4") (pin "2") (pinfunction "2_2") (pintype "passive"))
    )
    (net (code "65") (name "SWS_MAN_AUT") (class "Default")
      (node (ref "OK1_1") (pin "2") (pinfunction "C_2") (pintype "passive"))
      (node (ref "OK2_1") (pin "2") (pinfunction "C_2") (pintype "passive"))
      (node (ref "OK3_1") (pin "2") (pinfunction "C_2") (pintype "passive"))
      (node (ref "OK4_1") (pin "2") (pinfunction "C_2") (pintype "passive"))
      (node (ref "OK5_1") (pin "2") (pinfunction "C_2") (pintype "passive"))
      (node (ref "OK6_1") (pin "2") (pinfunction "C_2") (pintype "passive"))
      (node (ref "SV3") (pin "2") (pinfunction "2_2") (pintype "passive"))
    )
    (net (code "66") (name "VCC") (class "Default")
      (node (ref "C1_1") (pin "+") (pinfunction "+_+") (pintype "passive"))
      (node (ref "C2_1") (pin "+") (pinfunction "+_+") (pintype "passive"))
      (node (ref "C3_1") (pin "+") (pinfunction "+_+") (pintype "passive"))
      (node (ref "C4_1") (pin "+") (pinfunction "+_+") (pintype "passive"))
      (node (ref "C5_1") (pin "+") (pinfunction "+_+") (pintype "passive"))
      (node (ref "C6_1") (pin "+") (pinfunction "+_+") (pintype "passive"))
      (node (ref "OK1_2") (pin "1") (pinfunction "A_1") (pintype "passive"))
      (node (ref "OK2_2") (pin "1") (pinfunction "A_1") (pintype "passive"))
      (node (ref "OK3_2") (pin "1") (pinfunction "A_1") (pintype "passive"))
      (node (ref "OK4_2") (pin "1") (pinfunction "A_1") (pintype "passive"))
      (node (ref "OK5_2") (pin "1") (pinfunction "A_1") (pintype "passive"))
      (node (ref "OK6_2") (pin "1") (pinfunction "A_1") (pintype "passive"))
      (node (ref "Q1_1") (pin "3") (pinfunction "S_3") (pintype "passive"))
      (node (ref "Q2_1") (pin "3") (pinfunction "S_3") (pintype "passive"))
      (node (ref "Q3_1") (pin "3") (pinfunction "S_3") (pintype "passive"))
      (node (ref "Q4_1") (pin "3") (pinfunction "S_3") (pintype "passive"))
      (node (ref "Q5_1") (pin "3") (pinfunction "S_3") (pintype "passive"))
      (node (ref "Q6_1") (pin "3") (pinfunction "S_3") (pintype "passive"))
      (node (ref "R1_2") (pin "2") (pinfunction "2_2") (pintype "passive"))
      (node (ref "R1_6") (pin "2") (pinfunction "2_2") (pintype "passive"))
      (node (ref "R2_2") (pin "2") (pinfunction "2_2") (pintype "passive"))
      (node (ref "R3_2") (pin "2") (pinfunction "2_2") (pintype "passive"))
      (node (ref "R4_2") (pin "2") (pinfunction "2_2") (pintype "passive"))
      (node (ref "R5_2") (pin "2") (pinfunction "2_2") (pintype "passive"))
      (node (ref "R6_2") (pin "2") (pinfunction "2_2") (pintype "passive"))
      (node (ref "X1") (pin "2") (pinfunction "KL_2") (pintype "passive"))
    )
    (net (code "67") (name "VDD") (class "Default")
      (node (ref "C1_IC1") (pin "1") (pinfunction "1_1") (pintype "passive"))
      (node (ref "C1_OK1_2") (pin "1") (pinfunction "1_1") (pintype "passive"))
      (node (ref "C1_OK4_2") (pin "1") (pinfunction "1_1") (pintype "passive"))
      (node (ref "C2_IC2") (pin "1") (pinfunction "1_1") (pintype "passive"))
      (node (ref "IC1") (pin "20") (pinfunction "VCC_20") (pintype "power_in"))
      (node (ref "IC2") (pin "20") (pinfunction "VCC_20") (pintype "power_in"))
      (node (ref "OK1_2") (pin "4") (pinfunction "COL_4") (pintype "passive"))
      (node (ref "OK2_2") (pin "4") (pinfunction "COL_4") (pintype "passive"))
      (node (ref "OK3_2") (pin "4") (pinfunction "COL_4") (pintype "passive"))
      (node (ref "OK4_2") (pin "4") (pinfunction "COL_4") (pintype "passive"))
      (node (ref "OK5_2") (pin "4") (pinfunction "COL_4") (pintype "passive"))
      (node (ref "OK6_2") (pin "4") (pinfunction "COL_4") (pintype "passive"))
      (node (ref "R1_7") (pin "2") (pinfunction "2_2") (pintype "passive"))
      (node (ref "SV3") (pin "25") (pinfunction "25_25") (pintype "passive"))
      (node (ref "SV3") (pin "26") (pinfunction "26_26") (pintype "passive"))
    )
    (net (code "68") (name "unconnected-(IC1-O3-Pad15)") (class "Default")
      (node (ref "IC1") (pin "15") (pinfunction "O3_15") (pintype "output"))
    )
    (net (code "69") (name "unconnected-(IC1-O4-Pad14)") (class "Default")
      (node (ref "IC1") (pin "14") (pinfunction "O4_14") (pintype "output"))
    )
    (net (code "70") (name "unconnected-(IC2-O3-Pad15)") (class "Default")
      (node (ref "IC2") (pin "15") (pinfunction "O3_15") (pintype "output"))
    )
    (net (code "71") (name "unconnected-(IC2-O4-Pad14)") (class "Default")
      (node (ref "IC2") (pin "14") (pinfunction "O4_14") (pintype "output"))
    )
    (net (code "72") (name "unconnected-(SV3-Pad3)") (class "Default")
      (node (ref "SV3") (pin "3") (pinfunction "3_3") (pintype "passive"))
    )
    (net (code "73") (name "unconnected-(SV3-Pad5)") (class "Default")
      (node (ref "SV3") (pin "5") (pinfunction "5_5") (pintype "passive"))
    )
    (net (code "74") (name "unconnected-(SV3-Pad7)") (class "Default")
      (node (ref "SV3") (pin "7") (pinfunction "7_7") (pintype "passive"))
    )
    (net (code "75") (name "unconnected-(SV3-Pad11)") (class "Default")
      (node (ref "SV3") (pin "11") (pinfunction "11_11") (pintype "passive"))
    )
    (net (code "76") (name "unconnected-(SV3-Pad13)") (class "Default")
      (node (ref "SV3") (pin "13") (pinfunction "13_13") (pintype "passive"))
    )
    (net (code "77") (name "unconnected-(SV3-Pad15)") (class "Default")
      (node (ref "SV3") (pin "15") (pinfunction "15_15") (pintype "passive"))
    )
    (net (code "78") (name "unconnected-(SV3-Pad19)") (class "Default")
      (node (ref "SV3") (pin "19") (pinfunction "19_19") (pintype "passive"))
    )
    (net (code "79") (name "unconnected-(SV3-Pad21)") (class "Default")
      (node (ref "SV3") (pin "21") (pinfunction "21_21") (pintype "passive"))
    )
    (net (code "80") (name "unconnected-(SV3-Pad23)") (class "Default")
      (node (ref "SV3") (pin "23") (pinfunction "23_23") (pintype "passive"))
    )
    (net (code "81") (name "unconnected-(SV3-Pad27)") (class "Default")
      (node (ref "SV3") (pin "27") (pinfunction "27_27") (pintype "passive"))
    )
    (net (code "82") (name "unconnected-(SV3-Pad29)") (class "Default")
      (node (ref "SV3") (pin "29") (pinfunction "29_29") (pintype "passive"))
    )
    (net (code "83") (name "unconnected-(SV3-Pad31)") (class "Default")
      (node (ref "SV3") (pin "31") (pinfunction "31_31") (pintype "passive"))
    )
    (net (code "84") (name "unconnected-(SV3-Pad35)") (class "Default")
      (node (ref "SV3") (pin "35") (pinfunction "35_35") (pintype "passive"))
    )
    (net (code "85") (name "unconnected-(SV3-Pad37)") (class "Default")
      (node (ref "SV3") (pin "37") (pinfunction "37_37") (pintype "passive"))
    )
    (net (code "86") (name "unconnected-(SV3-Pad39)") (class "Default")
      (node (ref "SV3") (pin "39") (pinfunction "39_39") (pintype "passive"))
    )
    (net (code "87") (name "unconnected-(SV3-Pad43)") (class "Default")
      (node (ref "SV3") (pin "43") (pinfunction "43_43") (pintype "passive"))
    )
    (net (code "88") (name "unconnected-(SV3-Pad45)") (class "Default")
      (node (ref "SV3") (pin "45") (pinfunction "45_45") (pintype "passive"))
    )
    (net (code "89") (name "unconnected-(SV3-Pad47)") (class "Default")
      (node (ref "SV3") (pin "47") (pinfunction "47_47") (pintype "passive"))
    )
  )
)
